# power.net
KiCad netlist of a schematic drawn in EAGLE
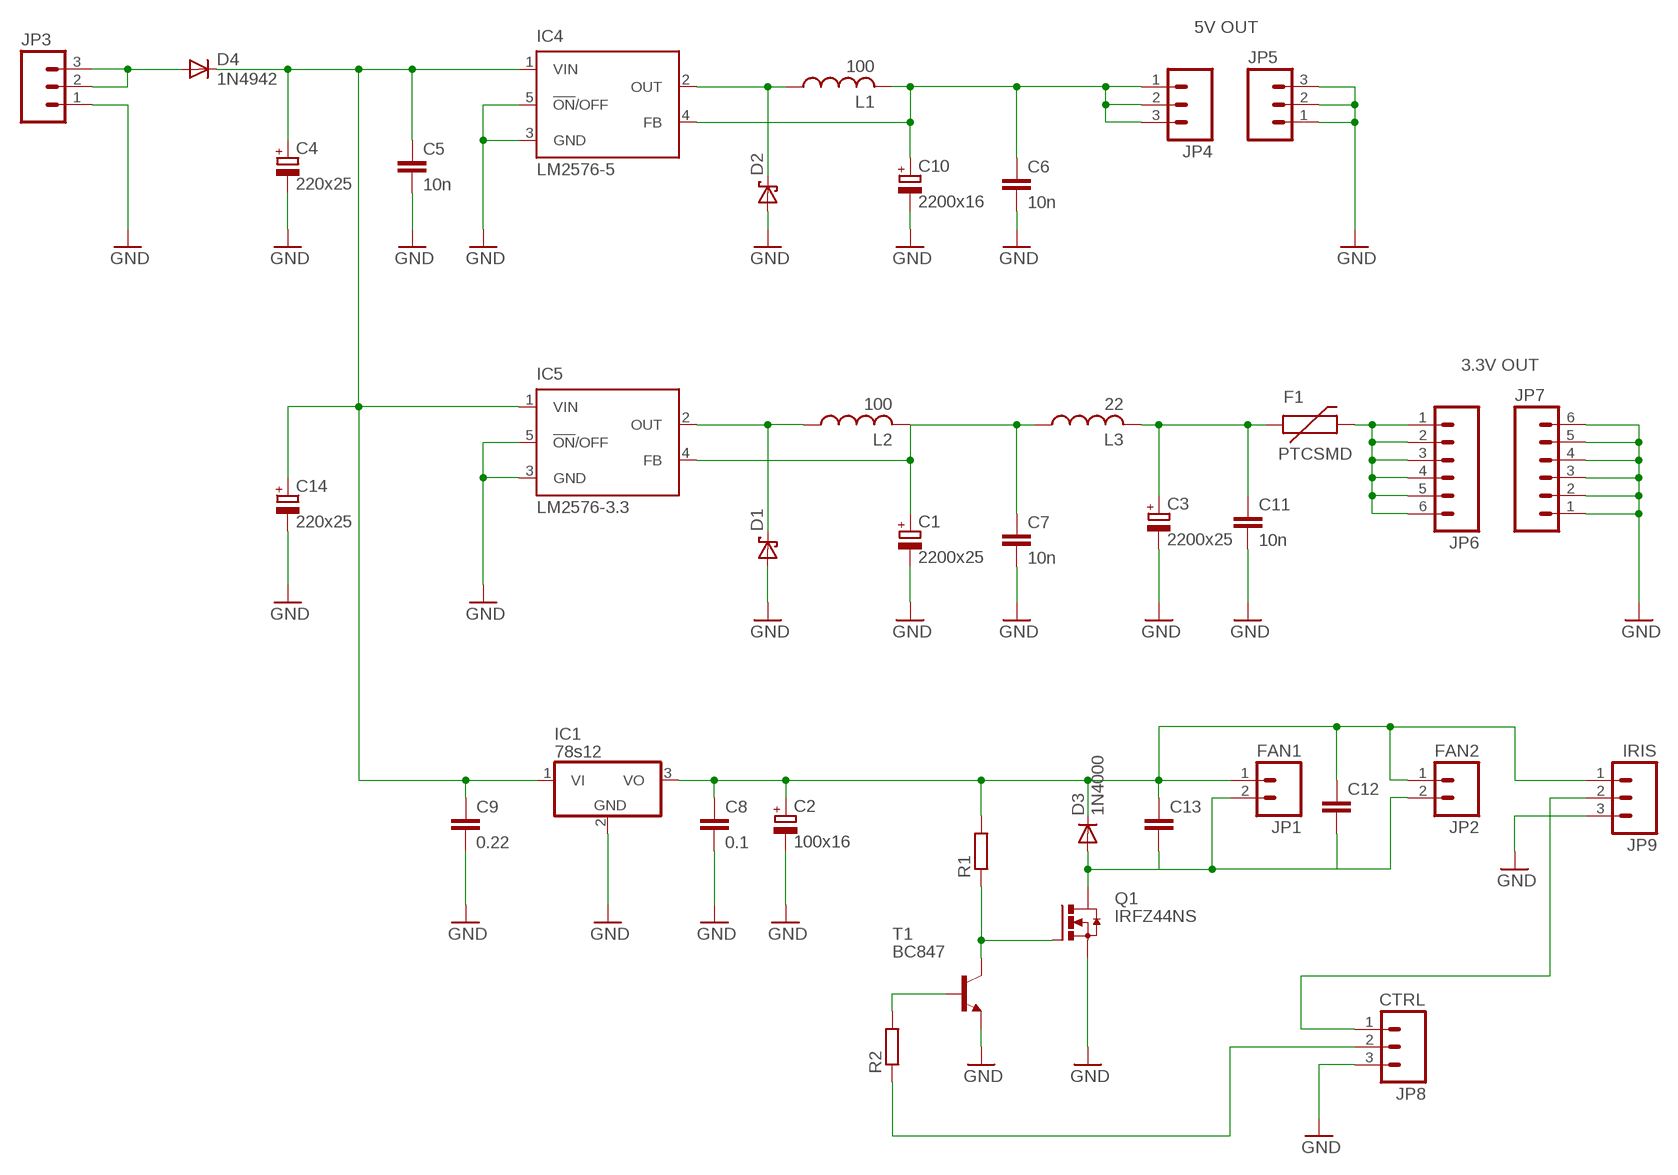
[diagram p0: schematic, sheet 1]

(export (version "E")
  (design (tool "Eeschema 10.0.6"))
  (components
    (comp (ref "C1")
      (value "2200x25")
      (footprint "eagle-import:E3,5-10")
      (libsource (lib "eagle-import") (part "CPOL-EUE3.5-10"))
    )
    (comp (ref "C2")
      (value "100x16")
      (footprint "eagle-import:E2,5-7")
      (libsource (lib "eagle-import") (part "CPOL-EUE2.5-7"))
    )
    (comp (ref "C3")
      (value "2200x25")
      (footprint "eagle-import:E3,5-10")
      (libsource (lib "eagle-import") (part "CPOL-EUE3.5-10"))
    )
    (comp (ref "C4")
      (value "220x25")
      (footprint "eagle-import:E3,5-10")
      (libsource (lib "eagle-import") (part "CPOL-EUE3.5-10"))
    )
    (comp (ref "C5")
      (value "10n")
      (footprint "eagle-import:0805")
      (libsource (lib "eagle-import") (part "CAP0805"))
    )
    (comp (ref "C6")
      (value "10n")
      (footprint "eagle-import:0805")
      (libsource (lib "eagle-import") (part "CAP0805"))
    )
    (comp (ref "C7")
      (value "10n")
      (footprint "eagle-import:0805")
      (libsource (lib "eagle-import") (part "CAP0805"))
    )
    (comp (ref "C8")
      (value "0.1")
      (footprint "eagle-import:0805")
      (libsource (lib "eagle-import") (part "CAP0805"))
    )
    (comp (ref "C9")
      (value "0.22")
      (footprint "eagle-import:0805")
      (libsource (lib "eagle-import") (part "CAP0805"))
    )
    (comp (ref "C10")
      (value "2200x16")
      (footprint "eagle-import:E3,5-10")
      (libsource (lib "eagle-import") (part "CPOL-EUE3.5-10"))
    )
    (comp (ref "C11")
      (value "10n")
      (footprint "eagle-import:0805")
      (libsource (lib "eagle-import") (part "CAP0805"))
    )
    (comp (ref "C12")
      (value "C-EUC0805K")
      (footprint "eagle-import:C0805K")
      (libsource (lib "eagle-import") (part "C-EUC0805K"))
    )
    (comp (ref "C13")
      (value "C-EUC0805K")
      (footprint "eagle-import:C0805K")
      (libsource (lib "eagle-import") (part "C-EUC0805K"))
    )
    (comp (ref "C14")
      (value "220x25")
      (footprint "eagle-import:E3,5-10")
      (libsource (lib "eagle-import") (part "CPOL-EUE3.5-10"))
    )
    (comp (ref "D1")
      (value "DS_E2L")
      (footprint "eagle-import:E2LINE")
      (libsource (lib "eagle-import") (part "DS_E2L"))
    )
    (comp (ref "D2")
      (value "DS_E2L")
      (footprint "eagle-import:E2LINE")
      (libsource (lib "eagle-import") (part "DS_E2L"))
    )
    (comp (ref "D3")
      (value "1N4000")
      (footprint "eagle-import:DO41-10")
      (libsource (lib "eagle-import") (part "1N4004"))
    )
    (comp (ref "D4")
      (value "1N4942")
      (footprint "eagle-import:DO41-10")
      (libsource (lib "eagle-import") (part "1N4942"))
    )
    (comp (ref "F1")
      (value "PTCSMD")
      (footprint "eagle-import:PTC-1206")
      (libsource (lib "eagle-import") (part "PTCSMD"))
    )
    (comp (ref "IC1")
      (value "78s12")
      (footprint "eagle-import:TO220H")
      (libsource (lib "eagle-import") (part "78T06"))
    )
    (comp (ref "IC4")
      (value "LM2576-5")
      (footprint "eagle-import:TO263-5")
      (fields (field (name "MF") "NATIONAL SEMICONDUCTOR") (field (name "MPN") "LM2596S-ADJ/NOPB"))
      (libsource (lib "eagle-import") (part "LM2596S"))
    )
    (comp (ref "IC5")
      (value "LM2576-3.3")
      (footprint "eagle-import:TO263-5")
      (fields (field (name "MF") "NATIONAL SEMICONDUCTOR") (field (name "MPN") "LM2596S-ADJ/NOPB"))
      (libsource (lib "eagle-import") (part "LM2596S"))
    )
    (comp (ref "JP1")
      (value "FAN1")
      (footprint "eagle-import:JST-2-PTH-VERT")
      (libsource (lib "eagle-import") (part "M02JST-PTH-VERT"))
    )
    (comp (ref "JP2")
      (value "FAN2")
      (footprint "eagle-import:JST-2-PTH-VERT")
      (libsource (lib "eagle-import") (part "M02JST-PTH-VERT"))
    )
    (comp (ref "JP3")
      (value "M03JST-PTH-VERT")
      (footprint "eagle-import:JST-3-PTH-VERT")
      (libsource (lib "eagle-import") (part "M03JST-PTH-VERT"))
    )
    (comp (ref "JP4")
      (value "M03LOCK")
      (footprint "eagle-import:1X03_LOCK")
      (libsource (lib "eagle-import") (part "M03LOCK"))
    )
    (comp (ref "JP5")
      (value "M03LOCK")
      (footprint "eagle-import:1X03_LOCK")
      (libsource (lib "eagle-import") (part "M03LOCK"))
    )
    (comp (ref "JP6")
      (value "M06LOCK")
      (footprint "eagle-import:1X06_LOCK")
      (libsource (lib "eagle-import") (part "M06LOCK"))
    )
    (comp (ref "JP7")
      (value "M06LOCK")
      (footprint "eagle-import:1X06_LOCK")
      (libsource (lib "eagle-import") (part "M06LOCK"))
    )
    (comp (ref "JP8")
      (value "CTRL")
      (footprint "eagle-import:1X03")
      (libsource (lib "eagle-import") (part "M03PTH"))
    )
    (comp (ref "JP9")
      (value "IRIS")
      (footprint "eagle-import:1X03")
      (libsource (lib "eagle-import") (part "M03PTH"))
    )
    (comp (ref "L1")
      (value "100")
      (footprint "eagle-import:L8530M")
      (libsource (lib "eagle-import") (part "L-USL8530M"))
    )
    (comp (ref "L2")
      (value "100")
      (footprint "eagle-import:L8530M")
      (libsource (lib "eagle-import") (part "L-USL8530M"))
    )
    (comp (ref "L3")
      (value "22")
      (footprint "eagle-import:L8530M")
      (libsource (lib "eagle-import") (part "L-USL8530M"))
    )
    (comp (ref "Q1")
      (value "IRFZ44NS")
      (footprint "eagle-import:D2PACK")
      (libsource (lib "eagle-import") (part "IRF3704S"))
    )
    (comp (ref "R1")
      (value "R-EU_R0805")
      (footprint "eagle-import:R0805")
      (libsource (lib "eagle-import") (part "R-EU_R0805"))
    )
    (comp (ref "R2")
      (value "R-EU_R0805")
      (footprint "eagle-import:R0805")
      (libsource (lib "eagle-import") (part "R-EU_R0805"))
    )
    (comp (ref "T1")
      (value "BC847")
      (footprint "eagle-import:SOT23")
      (libsource (lib "eagle-import") (part "BC847"))
    )
  )
  (nets
    (net (code "1") (name "GND") (class "Default")
      (node (ref "C1") (pin "-") (pinfunction "-_-") (pintype "passive"))
      (node (ref "C10") (pin "-") (pinfunction "-_-") (pintype "passive"))
      (node (ref "C11") (pin "2") (pinfunction "2_2") (pintype "passive"))
      (node (ref "C14") (pin "-") (pinfunction "-_-") (pintype "passive"))
      (node (ref "C2") (pin "-") (pinfunction "-_-") (pintype "passive"))
      (node (ref "C3") (pin "-") (pinfunction "-_-") (pintype "passive"))
      (node (ref "C4") (pin "-") (pinfunction "-_-") (pintype "passive"))
      (node (ref "C5") (pin "2") (pinfunction "2_2") (pintype "passive"))
      (node (ref "C6") (pin "2") (pinfunction "2_2") (pintype "passive"))
      (node (ref "C7") (pin "2") (pinfunction "2_2") (pintype "passive"))
      (node (ref "C8") (pin "2") (pinfunction "2_2") (pintype "passive"))
      (node (ref "C9") (pin "2") (pinfunction "2_2") (pintype "passive"))
      (node (ref "D1") (pin "2") (pinfunction "A_2") (pintype "passive"))
      (node (ref "D2") (pin "2") (pinfunction "A_2") (pintype "passive"))
      (node (ref "IC1") (pin "2") (pinfunction "GND_2") (pintype "passive"))
      (node (ref "IC4") (pin "3") (pinfunction "GND_3") (pintype "power_in"))
      (node (ref "IC4") (pin "5") (pinfunction "~{ON}/OFF_5") (pintype "input"))
      (node (ref "IC5") (pin "3") (pinfunction "GND_3") (pintype "power_in"))
      (node (ref "IC5") (pin "5") (pinfunction "~{ON}/OFF_5") (pintype "input"))
      (node (ref "JP3") (pin "1") (pinfunction "1_1") (pintype "passive"))
      (node (ref "JP5") (pin "1") (pinfunction "1_1") (pintype "passive"))
      (node (ref "JP5") (pin "2") (pinfunction "2_2") (pintype "passive"))
      (node (ref "JP5") (pin "3") (pinfunction "3_3") (pintype "passive"))
      (node (ref "JP7") (pin "1") (pinfunction "1_1") (pintype "passive"))
      (node (ref "JP7") (pin "2") (pinfunction "2_2") (pintype "passive"))
      (node (ref "JP7") (pin "3") (pinfunction "3_3") (pintype "passive"))
      (node (ref "JP7") (pin "4") (pinfunction "4_4") (pintype "passive"))
      (node (ref "JP7") (pin "5") (pinfunction "5_5") (pintype "passive"))
      (node (ref "JP7") (pin "6") (pinfunction "6_6") (pintype "passive"))
      (node (ref "JP8") (pin "3") (pinfunction "3_3") (pintype "passive"))
      (node (ref "JP9") (pin "3") (pinfunction "3_3") (pintype "passive"))
      (node (ref "Q1") (pin "3") (pinfunction "S_3") (pintype "passive"))
      (node (ref "T1") (pin "2") (pinfunction "E_2") (pintype "passive"))
    )
    (net (code "2") (name "Net-(C11-Pad1)") (class "Default")
      (node (ref "C11") (pin "1") (pinfunction "1_1") (pintype "passive"))
      (node (ref "C3") (pin "+") (pinfunction "+_+") (pintype "passive"))
      (node (ref "F1") (pin "1") (pinfunction "1_1") (pintype "bidirectional"))
      (node (ref "L3") (pin "2") (pinfunction "2_2") (pintype "passive"))
    )
    (net (code "3") (name "Net-(D1-K)") (class "Default")
      (node (ref "D1") (pin "1") (pinfunction "K_1") (pintype "passive"))
      (node (ref "IC5") (pin "2") (pinfunction "OUT_2") (pintype "output"))
      (node (ref "L2") (pin "1") (pinfunction "1_1") (pintype "passive"))
    )
    (net (code "4") (name "Net-(D2-K)") (class "Default")
      (node (ref "D2") (pin "1") (pinfunction "K_1") (pintype "passive"))
      (node (ref "IC4") (pin "2") (pinfunction "OUT_2") (pintype "output"))
      (node (ref "L1") (pin "1") (pinfunction "1_1") (pintype "passive"))
    )
    (net (code "5") (name "Net-(D4-PadA)") (class "Default")
      (node (ref "D4") (pin "A") (pinfunction "A_A") (pintype "passive"))
      (node (ref "JP3") (pin "2") (pinfunction "2_2") (pintype "passive"))
      (node (ref "JP3") (pin "3") (pinfunction "3_3") (pintype "passive"))
    )
    (net (code "6") (name "Net-(F1-Pad2)") (class "Default")
      (node (ref "F1") (pin "2") (pinfunction "2_2") (pintype "bidirectional"))
      (node (ref "JP6") (pin "1") (pinfunction "1_1") (pintype "passive"))
      (node (ref "JP6") (pin "2") (pinfunction "2_2") (pintype "passive"))
      (node (ref "JP6") (pin "3") (pinfunction "3_3") (pintype "passive"))
      (node (ref "JP6") (pin "4") (pinfunction "4_4") (pintype "passive"))
      (node (ref "JP6") (pin "5") (pinfunction "5_5") (pintype "passive"))
      (node (ref "JP6") (pin "6") (pinfunction "6_6") (pintype "passive"))
    )
    (net (code "7") (name "Net-(IC1-VI)") (class "Default")
      (node (ref "C14") (pin "+") (pinfunction "+_+") (pintype "passive"))
      (node (ref "C4") (pin "+") (pinfunction "+_+") (pintype "passive"))
      (node (ref "C5") (pin "1") (pinfunction "1_1") (pintype "passive"))
      (node (ref "C9") (pin "1") (pinfunction "1_1") (pintype "passive"))
      (node (ref "D4") (pin "C") (pinfunction "C_C") (pintype "passive"))
      (node (ref "IC1") (pin "1") (pinfunction "VI_1") (pintype "input"))
      (node (ref "IC4") (pin "1") (pinfunction "VIN_1") (pintype "input"))
      (node (ref "IC5") (pin "1") (pinfunction "VIN_1") (pintype "input"))
    )
    (net (code "8") (name "Net-(IC1-VO)") (class "Default")
      (node (ref "C12") (pin "1") (pinfunction "1_1") (pintype "passive"))
      (node (ref "C13") (pin "1") (pinfunction "1_1") (pintype "passive"))
      (node (ref "C2") (pin "+") (pinfunction "+_+") (pintype "passive"))
      (node (ref "C8") (pin "1") (pinfunction "1_1") (pintype "passive"))
      (node (ref "D3") (pin "C") (pinfunction "C_C") (pintype "passive"))
      (node (ref "IC1") (pin "3") (pinfunction "VO_3") (pintype "passive"))
      (node (ref "JP1") (pin "1") (pinfunction "1_1") (pintype "passive"))
      (node (ref "JP2") (pin "1") (pinfunction "1_1") (pintype "passive"))
      (node (ref "JP9") (pin "1") (pinfunction "1_1") (pintype "passive"))
      (node (ref "R1") (pin "2") (pinfunction "2_2") (pintype "passive"))
    )
    (net (code "9") (name "Net-(IC4-FB)") (class "Default")
      (node (ref "C10") (pin "+") (pinfunction "+_+") (pintype "passive"))
      (node (ref "C6") (pin "1") (pinfunction "1_1") (pintype "passive"))
      (node (ref "IC4") (pin "4") (pinfunction "FB_4") (pintype "input"))
      (node (ref "JP4") (pin "1") (pinfunction "1_1") (pintype "passive"))
      (node (ref "JP4") (pin "2") (pinfunction "2_2") (pintype "passive"))
      (node (ref "JP4") (pin "3") (pinfunction "3_3") (pintype "passive"))
      (node (ref "L1") (pin "2") (pinfunction "2_2") (pintype "passive"))
    )
    (net (code "10") (name "Net-(IC5-FB)") (class "Default")
      (node (ref "C1") (pin "+") (pinfunction "+_+") (pintype "passive"))
      (node (ref "C7") (pin "1") (pinfunction "1_1") (pintype "passive"))
      (node (ref "IC5") (pin "4") (pinfunction "FB_4") (pintype "input"))
      (node (ref "L2") (pin "2") (pinfunction "2_2") (pintype "passive"))
      (node (ref "L3") (pin "1") (pinfunction "1_1") (pintype "passive"))
    )
    (net (code "11") (name "Net-(JP8-Pad1)") (class "Default")
      (node (ref "JP8") (pin "1") (pinfunction "1_1") (pintype "passive"))
      (node (ref "JP9") (pin "2") (pinfunction "2_2") (pintype "passive"))
    )
    (net (code "12") (name "Net-(JP8-Pad2)") (class "Default")
      (node (ref "JP8") (pin "2") (pinfunction "2_2") (pintype "passive"))
      (node (ref "R2") (pin "1") (pinfunction "1_1") (pintype "passive"))
    )
    (net (code "13") (name "Net-(Q1-D)") (class "Default")
      (node (ref "C12") (pin "2") (pinfunction "2_2") (pintype "passive"))
      (node (ref "C13") (pin "2") (pinfunction "2_2") (pintype "passive"))
      (node (ref "D3") (pin "A") (pinfunction "A_A") (pintype "passive"))
      (node (ref "JP1") (pin "2") (pinfunction "2_2") (pintype "passive"))
      (node (ref "JP2") (pin "2") (pinfunction "2_2") (pintype "passive"))
      (node (ref "Q1") (pin "2") (pinfunction "D_2") (pintype "passive"))
    )
    (net (code "14") (name "Net-(Q1-G)") (class "Default")
      (node (ref "Q1") (pin "1") (pinfunction "G_1") (pintype "passive"))
      (node (ref "R1") (pin "1") (pinfunction "1_1") (pintype "passive"))
      (node (ref "T1") (pin "3") (pinfunction "C_3") (pintype "passive"))
    )
    (net (code "15") (name "Net-(T1-B)") (class "Default")
      (node (ref "R2") (pin "2") (pinfunction "2_2") (pintype "passive"))
      (node (ref "T1") (pin "1") (pinfunction "B_1") (pintype "passive"))
    )
  )
)
